# laserdriver_v3_2.net
KiCad netlist of a schematic drawn in EAGLE
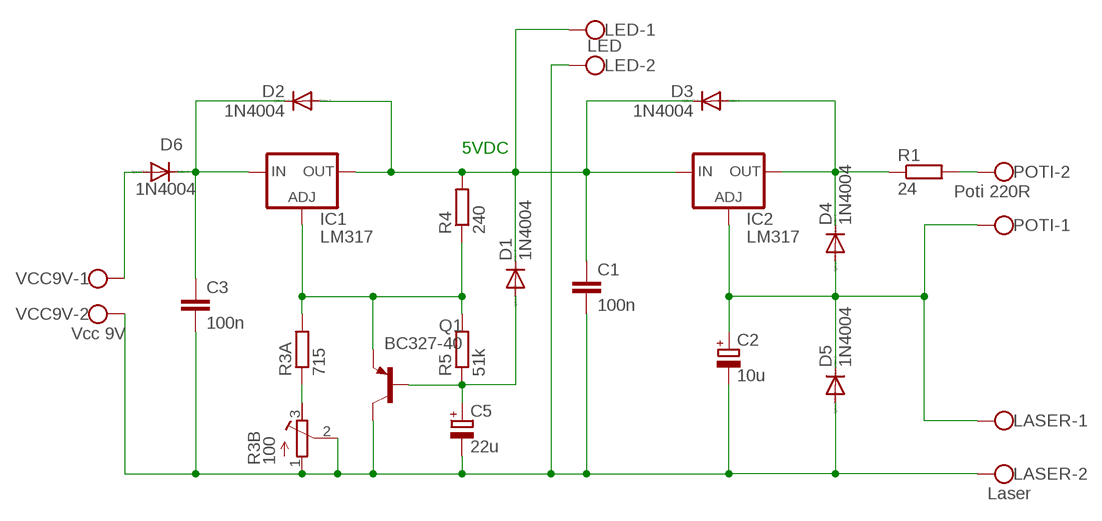
[diagram p0: schematic, sheet 1]

(export (version "E")
  (design (tool "Eeschema 10.0.6"))
  (components
    (comp (ref "C1")
      (value "100n")
      (footprint "eagle-import:C050-024X044")
      (libsource (lib "eagle-import") (part "C-EU050-024X044"))
    )
    (comp (ref "C2")
      (value "10u")
      (footprint "eagle-import:E2-5")
      (libsource (lib "eagle-import") (part "CPOL-EUE2-5"))
    )
    (comp (ref "C3")
      (value "100n")
      (footprint "eagle-import:C050-024X044")
      (libsource (lib "eagle-import") (part "C-EU050-024X044"))
    )
    (comp (ref "C5")
      (value "22u")
      (footprint "eagle-import:E2-5")
      (libsource (lib "eagle-import") (part "CPOL-EUE2-5"))
    )
    (comp (ref "D1")
      (value "1N4004")
      (footprint "eagle-import:DO41-10")
      (libsource (lib "eagle-import") (part "1N4004"))
    )
    (comp (ref "D2")
      (value "1N4004")
      (footprint "eagle-import:DO41-10")
      (libsource (lib "eagle-import") (part "1N4004"))
    )
    (comp (ref "D3")
      (value "1N4004")
      (footprint "eagle-import:DO41-10")
      (libsource (lib "eagle-import") (part "1N4004"))
    )
    (comp (ref "D4")
      (value "1N4004")
      (footprint "eagle-import:DO41-10")
      (libsource (lib "eagle-import") (part "1N4004"))
    )
    (comp (ref "D5")
      (value "1N4004")
      (footprint "eagle-import:DO41-10")
      (libsource (lib "eagle-import") (part "1N4004"))
    )
    (comp (ref "D6")
      (value "1N4004")
      (footprint "eagle-import:DO41-10")
      (libsource (lib "eagle-import") (part "1N4004"))
    )
    (comp (ref "IC1")
      (value "LM317")
      (footprint "eagle-import:317TS")
      (libsource (lib "eagle-import") (part "LM317TS"))
    )
    (comp (ref "IC2")
      (value "LM317")
      (footprint "eagle-import:317TS")
      (libsource (lib "eagle-import") (part "LM317TS"))
    )
    (comp (ref "LASER")
      (value "Laser")
      (footprint "eagle-import:W237-102")
      (fields (field (name "MPN") "237-102"))
      (libsource (lib "eagle-import") (part "W237-102"))
    )
    (comp (ref "LED")
      (value "LED")
      (footprint "eagle-import:W237-102")
      (fields (field (name "MPN") "237-102"))
      (libsource (lib "eagle-import") (part "W237-102"))
    )
    (comp (ref "POTI")
      (value "Poti 220R")
      (footprint "eagle-import:W237-102")
      (fields (field (name "MPN") "237-102"))
      (libsource (lib "eagle-import") (part "W237-102"))
    )
    (comp (ref "Q1")
      (value "BC327-40")
      (footprint "eagle-import:TO92-EBC")
      (libsource (lib "eagle-import") (part "BC327-40"))
    )
    (comp (ref "R1")
      (value "24")
      (footprint "eagle-import:0207_7")
      (libsource (lib "eagle-import") (part "R-EU_0207/7"))
    )
    (comp (ref "R3A")
      (value "715")
      (footprint "eagle-import:0207_7")
      (libsource (lib "eagle-import") (part "R-EU_0207/7"))
    )
    (comp (ref "R3B")
      (value "100")
      (footprint "eagle-import:RTRIM3296W")
      (libsource (lib "eagle-import") (part "R-TRIMM3296W"))
    )
    (comp (ref "R4")
      (value "240")
      (footprint "eagle-import:0207_7")
      (libsource (lib "eagle-import") (part "R-EU_0207/7"))
    )
    (comp (ref "R5")
      (value "51k")
      (footprint "eagle-import:0207_7")
      (libsource (lib "eagle-import") (part "R-EU_0207/7"))
    )
    (comp (ref "VCC9V")
      (value "Vcc 9V")
      (footprint "eagle-import:W237-102")
      (fields (field (name "MPN") "237-102"))
      (libsource (lib "eagle-import") (part "W237-102"))
    )
  )
  (nets
    (net (code "1") (name "Net-(C5-Pad+)") (class "Default")
      (node (ref "C5") (pin "+") (pinfunction "+_+") (pintype "passive"))
      (node (ref "D1") (pin "A") (pinfunction "A_A") (pintype "passive"))
      (node (ref "Q1") (pin "B") (pinfunction "B_B") (pintype "passive"))
      (node (ref "R5") (pin "1") (pinfunction "1_1") (pintype "passive"))
    )
    (net (code "2") (name "Net-(IC1-ADJ)") (class "Default")
      (node (ref "IC1") (pin "1") (pinfunction "ADJ_1") (pintype "input"))
      (node (ref "Q1") (pin "E") (pinfunction "E_E") (pintype "passive"))
      (node (ref "R3A") (pin "2") (pinfunction "2_2") (pintype "passive"))
      (node (ref "R4") (pin "1") (pinfunction "1_1") (pintype "passive"))
      (node (ref "R5") (pin "2") (pinfunction "2_2") (pintype "passive"))
    )
    (net (code "3") (name "Net-(IC1-IN)") (class "Default")
      (node (ref "C3") (pin "1") (pinfunction "1_1") (pintype "passive"))
      (node (ref "D2") (pin "C") (pinfunction "C_C") (pintype "passive"))
      (node (ref "D6") (pin "C") (pinfunction "C_C") (pintype "passive"))
      (node (ref "IC1") (pin "3") (pinfunction "IN_3") (pintype "input"))
    )
    (net (code "4") (name "Net-(IC1-OUT)") (class "Default")
      (node (ref "C1") (pin "1") (pinfunction "1_1") (pintype "passive"))
      (node (ref "D1") (pin "C") (pinfunction "C_C") (pintype "passive"))
      (node (ref "D2") (pin "A") (pinfunction "A_A") (pintype "passive"))
      (node (ref "D3") (pin "C") (pinfunction "C_C") (pintype "passive"))
      (node (ref "IC1") (pin "2") (pinfunction "OUT_2") (pintype "passive"))
      (node (ref "IC2") (pin "3") (pinfunction "IN_3") (pintype "input"))
      (node (ref "LED") (pin "1") (pinfunction "KL_1") (pintype "passive"))
      (node (ref "R4") (pin "2") (pinfunction "2_2") (pintype "passive"))
    )
    (net (code "5") (name "Net-(IC2-ADJ)") (class "Default")
      (node (ref "C2") (pin "+") (pinfunction "+_+") (pintype "passive"))
      (node (ref "D4") (pin "A") (pinfunction "A_A") (pintype "passive"))
      (node (ref "D5") (pin "C") (pinfunction "C_C") (pintype "passive"))
      (node (ref "IC2") (pin "1") (pinfunction "ADJ_1") (pintype "input"))
      (node (ref "LASER") (pin "1") (pinfunction "KL_1") (pintype "passive"))
      (node (ref "POTI") (pin "1") (pinfunction "KL_1") (pintype "passive"))
    )
    (net (code "6") (name "Net-(IC2-OUT)") (class "Default")
      (node (ref "D3") (pin "A") (pinfunction "A_A") (pintype "passive"))
      (node (ref "D4") (pin "C") (pinfunction "C_C") (pintype "passive"))
      (node (ref "IC2") (pin "2") (pinfunction "OUT_2") (pintype "passive"))
      (node (ref "R1") (pin "1") (pinfunction "1_1") (pintype "passive"))
    )
    (net (code "7") (name "Net-(LASERB-KL)") (class "Default")
      (node (ref "C1") (pin "2") (pinfunction "2_2") (pintype "passive"))
      (node (ref "C2") (pin "-") (pinfunction "-_-") (pintype "passive"))
      (node (ref "C3") (pin "2") (pinfunction "2_2") (pintype "passive"))
      (node (ref "C5") (pin "-") (pinfunction "-_-") (pintype "passive"))
      (node (ref "D5") (pin "A") (pinfunction "A_A") (pintype "passive"))
      (node (ref "LASER") (pin "2") (pinfunction "KL_2") (pintype "passive"))
      (node (ref "LED") (pin "2") (pinfunction "KL_2") (pintype "passive"))
      (node (ref "Q1") (pin "C") (pinfunction "C_C") (pintype "passive"))
      (node (ref "R3B") (pin "1") (pinfunction "A_1") (pintype "passive"))
      (node (ref "R3B") (pin "2") (pinfunction "S_2") (pintype "passive"))
      (node (ref "VCC9V") (pin "2") (pinfunction "KL_2") (pintype "passive"))
    )
    (net (code "8") (name "Net-(POTIB-KL)") (class "Default")
      (node (ref "POTI") (pin "2") (pinfunction "KL_2") (pintype "passive"))
      (node (ref "R1") (pin "2") (pinfunction "2_2") (pintype "passive"))
    )
    (net (code "9") (name "Net-(R3B-E)") (class "Default")
      (node (ref "R3A") (pin "1") (pinfunction "1_1") (pintype "passive"))
      (node (ref "R3B") (pin "3") (pinfunction "E_3") (pintype "passive"))
    )
    (net (code "10") (name "Net-(VCC9VA-KL)") (class "Default")
      (node (ref "D6") (pin "A") (pinfunction "A_A") (pintype "passive"))
      (node (ref "VCC9V") (pin "1") (pinfunction "KL_1") (pintype "passive"))
    )
  )
)
